# Control_Board_Control.net
KiCad netlist of a schematic drawn in Altium Designer
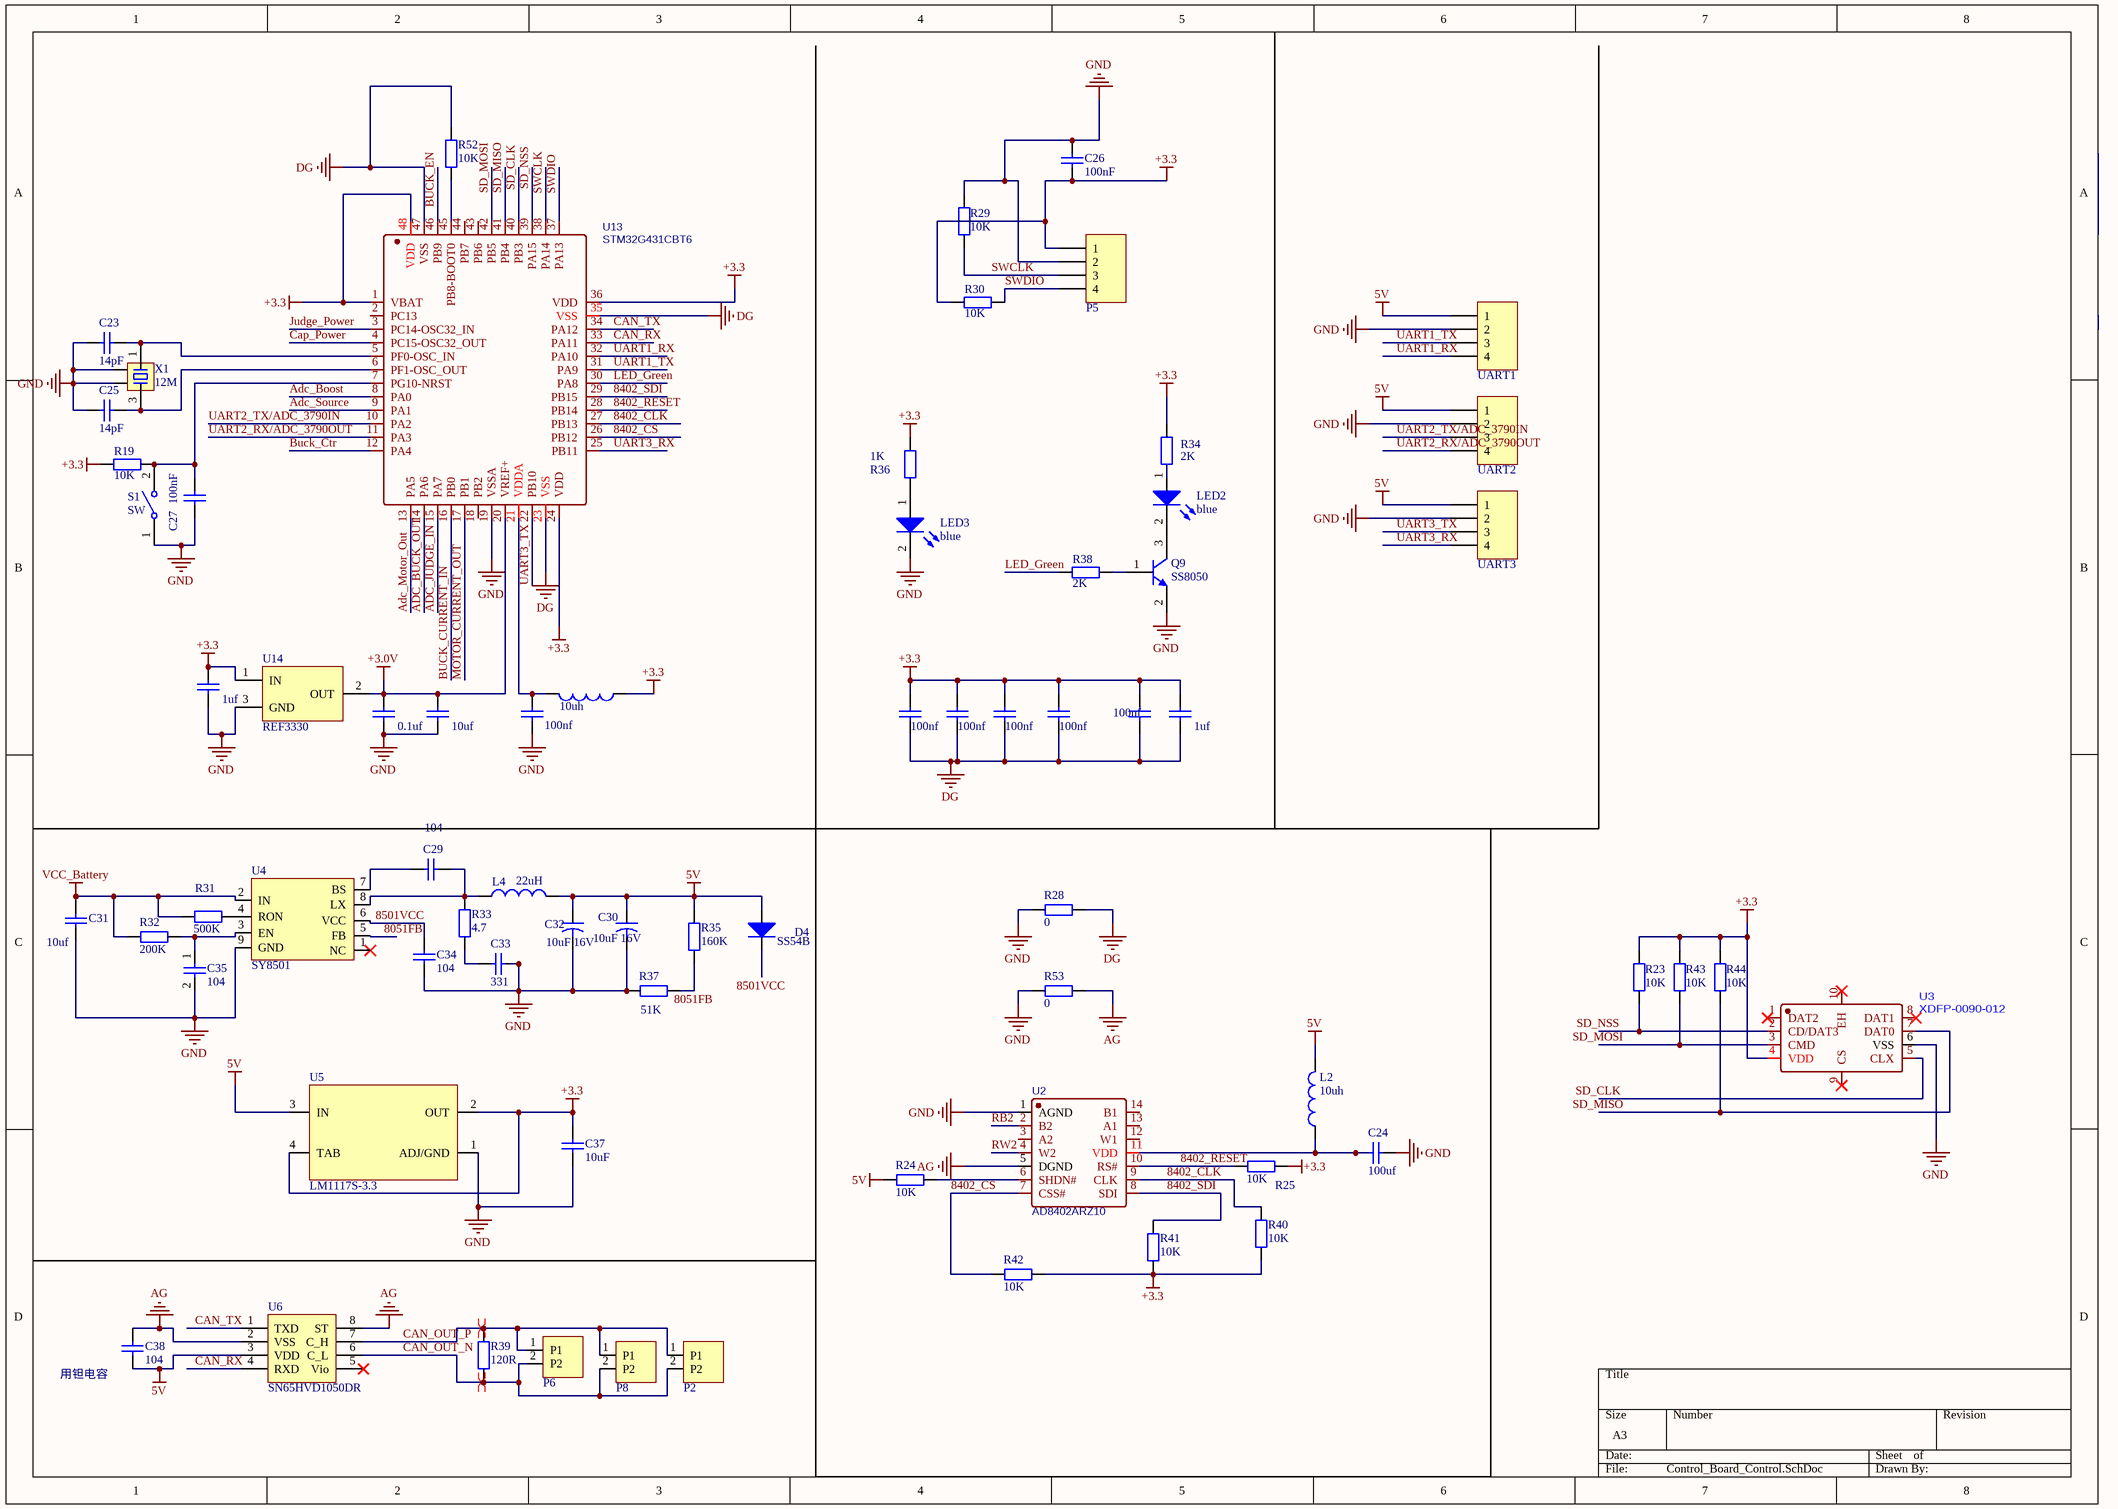
[diagram p0: Control_Board_Control.SchDoc]

(export (version "E")
  (design (tool "Eeschema 10.0.6"))
  (components
    (comp (ref "C23")
      (value "14pF")
      (footprint "c0402")
      (description "无极性电容")
      (fields (field (name "Comment") "27pf") (field (name "PUBLISHER") "Altium Limited"))
      (libsource (lib "Fszhang") (part "Cap"))
    )
    (comp (ref "C24")
      (value "100uf")
      (footprint "1210C")
      (description "无极性电容")
      (fields (field (name "PUBLISHER") "Altium Limited"))
      (libsource (lib "Fszhang") (part "Cap"))
    )
    (comp (ref "C25")
      (value "14pF")
      (footprint "c0402")
      (description "无极性电容")
      (fields (field (name "Comment") "27pf") (field (name "PUBLISHER") "Altium Limited"))
      (libsource (lib "Fszhang") (part "Cap"))
    )
    (comp (ref "C26")
      (value "100nF")
      (footprint "r0402")
      (description "无极性电容")
      (fields (field (name "PUBLISHER") "Altium Limited"))
      (libsource (lib "Fszhang") (part "Cap"))
    )
    (comp (ref "C27")
      (value "100nF")
      (footprint "c0402")
      (description "无极性电容")
      (fields (field (name "Comment") "100nf") (field (name "PUBLISHER") "Altium Limited"))
      (libsource (lib "Fszhang") (part "Cap"))
    )
    (comp (ref "C29")
      (value "104")
      (footprint "r0402")
      (description "无极性电容")
      (fields (field (name "PUBLISHER") "Altium Limited"))
      (libsource (lib "Fszhang") (part "Cap"))
    )
    (comp (ref "C30")
      (value "10uF 16V")
      (footprint "3216")
      (description "贴片电解")
      (fields (field (name "PUBLISHER") "Altium Limited"))
      (libsource (lib "Miscellaneous Devices") (part "Cap2"))
    )
    (comp (ref "C31")
      (value "10uf")
      (footprint "0805-1C")
      (description "无极性电容")
      (fields (field (name "PUBLISHER") "Altium Limited"))
      (libsource (lib "Fszhang") (part "Cap"))
    )
    (comp (ref "C32")
      (value "10uF 16V")
      (footprint "3216")
      (description "贴片电解")
      (fields (field (name "PUBLISHER") "Altium Limited"))
      (libsource (lib "Miscellaneous Devices") (part "Cap2"))
    )
    (comp (ref "C33")
      (value "331")
      (footprint "r0402")
      (description "无极性电容")
      (fields (field (name "PUBLISHER") "Altium Limited"))
      (libsource (lib "Fszhang") (part "Cap"))
    )
    (comp (ref "C34")
      (value "104")
      (footprint "r0402")
      (description "无极性电容")
      (fields (field (name "PUBLISHER") "Altium Limited"))
      (libsource (lib "Fszhang") (part "Cap"))
    )
    (comp (ref "C35")
      (value "104")
      (footprint "r0402")
      (description "贴片电容1206")
      (fields (field (name "C") "104"))
      (libsource (lib "原理图库") (part "CAP-W"))
    )
    (comp (ref "C36")
      (value "100nf")
      (footprint "c0402")
      (description "无极性电容")
      (fields (field (name "PUBLISHER") "Altium Limited"))
      (libsource (lib "Fszhang") (part "Cap"))
    )
    (comp (ref "C37")
      (value "10uF")
      (footprint "3216")
      (description "无极性电容")
      (fields (field (name "Comment") "10UF") (field (name "PUBLISHER") "Altium Limited"))
      (libsource (lib "Fszhang") (part "Cap"))
    )
    (comp (ref "C38")
      (value "104")
      (footprint "r0402")
      (description "贴片电容")
      (libsource (lib "0.1 - 电阻-电容-电感-电位器") (part "C"))
    )
    (comp (ref "C52")
      (value "100nf")
      (footprint "c0402")
      (description "无极性电容")
      (fields (field (name "PUBLISHER") "Altium Limited"))
      (libsource (lib "Fszhang") (part "Cap"))
    )
    (comp (ref "C53")
      (value "100nf")
      (footprint "c0402")
      (description "无极性电容")
      (fields (field (name "PUBLISHER") "Altium Limited"))
      (libsource (lib "Fszhang") (part "Cap"))
    )
    (comp (ref "C54")
      (value "100nf")
      (footprint "c0402")
      (description "无极性电容")
      (fields (field (name "PUBLISHER") "Altium Limited"))
      (libsource (lib "Fszhang") (part "Cap"))
    )
    (comp (ref "C55")
      (value "100nf")
      (footprint "c0402")
      (description "无极性电容")
      (fields (field (name "PUBLISHER") "Altium Limited"))
      (libsource (lib "Fszhang") (part "Cap"))
    )
    (comp (ref "C56")
      (value "100nf")
      (footprint "c0402")
      (description "无极性电容")
      (fields (field (name "PUBLISHER") "Altium Limited"))
      (libsource (lib "Fszhang") (part "Cap"))
    )
    (comp (ref "C57")
      (value "1uf")
      (footprint "c0402")
      (description "无极性电容")
      (fields (field (name "PUBLISHER") "Altium Limited"))
      (libsource (lib "Fszhang") (part "Cap"))
    )
    (comp (ref "C58")
      (value "1uf")
      (footprint "c0402")
      (description "无极性电容")
      (fields (field (name "PUBLISHER") "Altium Limited"))
      (libsource (lib "Fszhang") (part "Cap"))
    )
    (comp (ref "C63")
      (value "10uf")
      (footprint "c0402")
      (description "无极性电容")
      (fields (field (name "PUBLISHER") "Altium Limited"))
      (libsource (lib "Fszhang") (part "Cap"))
    )
    (comp (ref "C65")
      (value "0.1uf")
      (footprint "c0402")
      (description "无极性电容")
      (fields (field (name "PUBLISHER") "Altium Limited"))
      (libsource (lib "Fszhang") (part "Cap"))
    )
    (comp (ref "D4")
      (value "SS54B")
      (footprint "DO-214")
      (description "肖特基二极管")
      (fields (field (name "PUBLISHER") "Altium Limited"))
      (libsource (lib "Miscellaneous Devices") (part "Diode"))
    )
    (comp (ref "L2")
      (value "10uh")
      (footprint "l0805")
      (description "功率电感")
      (fields (field (name "PUBLISHER") "Altium Limited"))
      (libsource (lib "Miscellaneous Devices") (part "Inductor"))
    )
    (comp (ref "L4")
      (value "22uH")
      (footprint "CD54NP")
      (description "功率电感")
      (fields (field (name "PUBLISHER") "Altium Limited"))
      (libsource (lib "Miscellaneous Devices") (part "Inductor"))
    )
    (comp (ref "L8")
      (value "10uh")
      (footprint "l0805")
      (description "功率电感")
      (fields (field (name "PUBLISHER") "Altium Limited"))
      (libsource (lib "Miscellaneous Devices") (part "Inductor"))
    )
    (comp (ref "LED2")
      (value "LED_灯_黄")
      (footprint "led0805")
      (description "贴片LED")
      (fields (field (name "COLOR") "blue"))
      (libsource (lib "super_cap") (part "LED"))
    )
    (comp (ref "LED3")
      (value "LED_灯_黄")
      (footprint "led0805")
      (description "贴片LED")
      (fields (field (name "COLOR") "blue"))
      (libsource (lib "super_cap") (part "LED"))
    )
    (comp (ref "P2") (value "P2") (footprint "gh1.25") (libsource (lib "原理图库") (part "P2")))
    (comp (ref "P5")
      (value "Header 4")
      (footprint "gh1.25 4p 立贴")
      (description "排针")
      (fields (field (name "PUBLISHER") "Altium Limited"))
      (libsource (lib "super_cap") (part "Header 4"))
    )
    (comp (ref "P6") (value "P2") (footprint "gh1.25") (libsource (lib "原理图库") (part "P2")))
    (comp (ref "P8") (value "P2") (footprint "gh1.25") (libsource (lib "原理图库") (part "P2")))
    (comp (ref "Q9")
      (value "SS8050")
      (footprint "SOT-23")
      (description "NPN贴片三极管")
      (fields (field (name "PUBLISHER") "Altium Limited"))
      (libsource (lib "fszhang") (part "SS8050"))
    )
    (comp (ref "R19")
      (value "10K")
      (footprint "r0402")
      (description "贴片电阻")
      (fields (field (name "Comment") "10k") (field (name "PUBLISHER") "Altium Limited"))
      (libsource (lib "") (part "Res1_3"))
    )
    (comp (ref "R23")
      (value "10K")
      (footprint "R0402")
      (description "贴片电阻")
      (fields (field (name "PUBLISHER") "Altium Limited"))
      (libsource (lib "") (part "Res1_1"))
    )
    (comp (ref "R24")
      (value "10K")
      (footprint "r0402")
      (description "贴片电阻")
      (libsource (lib "super_cap") (part "R"))
    )
    (comp (ref "R25")
      (value "10K")
      (footprint "r0402")
      (description "贴片电阻")
      (libsource (lib "super_cap") (part "R"))
    )
    (comp (ref "R28")
      (value "0")
      (footprint "r0402")
      (description "贴片电阻")
      (libsource (lib "super_cap") (part "R"))
    )
    (comp (ref "R29")
      (value "10K")
      (footprint "r0402")
      (description "贴片电阻")
      (fields (field (name "PUBLISHER") "Altium Limited"))
      (libsource (lib "") (part "Res1_2"))
    )
    (comp (ref "R30")
      (value "10K")
      (footprint "r0402")
      (description "贴片电阻")
      (fields (field (name "PUBLISHER") "Altium Limited"))
      (libsource (lib "Fszhang") (part "Res1"))
    )
    (comp (ref "R31")
      (value "500K")
      (footprint "r0402")
      (description "贴片电阻")
      (libsource (lib "super_cap") (part "R"))
    )
    (comp (ref "R32")
      (value "200K")
      (footprint "r0402")
      (description "贴片电阻")
      (libsource (lib "super_cap") (part "R"))
    )
    (comp (ref "R33")
      (value "4.7")
      (footprint "r0402")
      (description "贴片电阻")
      (libsource (lib "super_cap") (part "R"))
    )
    (comp (ref "R34")
      (value "2K")
      (footprint "r0402")
      (description "贴片电阻")
      (fields (field (name "PUBLISHER") "Altium Limited"))
      (libsource (lib "") (part "Res1_2"))
    )
    (comp (ref "R35")
      (value "160K")
      (footprint "r0402")
      (description "贴片电阻")
      (libsource (lib "super_cap") (part "R"))
    )
    (comp (ref "R36")
      (value "1K")
      (footprint "r0402")
      (description "贴片电阻")
      (fields (field (name "PUBLISHER") "Altium Limited"))
      (libsource (lib "") (part "Res1_1"))
    )
    (comp (ref "R37")
      (value "51K")
      (footprint "r0402")
      (description "贴片电阻")
      (libsource (lib "super_cap") (part "R"))
    )
    (comp (ref "R38")
      (value "2K")
      (footprint "r0402")
      (description "贴片电阻")
      (fields (field (name "PUBLISHER") "Altium Limited"))
      (libsource (lib "Fszhang") (part "Res1"))
    )
    (comp (ref "R39")
      (value "120R")
      (footprint "r0402")
      (description "贴片电阻")
      (libsource (lib "0.1 - 电阻-电容-电感-电位器") (part "R"))
    )
    (comp (ref "R40")
      (value "10K")
      (footprint "r0402")
      (description "贴片电阻")
      (libsource (lib "super_cap") (part "R"))
    )
    (comp (ref "R41")
      (value "10K")
      (footprint "r0402")
      (description "贴片电阻")
      (libsource (lib "super_cap") (part "R"))
    )
    (comp (ref "R42")
      (value "10K")
      (footprint "r0402")
      (description "贴片电阻")
      (libsource (lib "super_cap") (part "R"))
    )
    (comp (ref "R43")
      (value "10K")
      (footprint "R0402")
      (description "贴片电阻")
      (fields (field (name "PUBLISHER") "Altium Limited"))
      (libsource (lib "") (part "Res1_1"))
    )
    (comp (ref "R44")
      (value "10K")
      (footprint "R0402")
      (description "贴片电阻")
      (fields (field (name "PUBLISHER") "Altium Limited"))
      (libsource (lib "") (part "Res1_1"))
    )
    (comp (ref "R52")
      (value "10K")
      (footprint "r0402")
      (description "贴片电阻")
      (libsource (lib "super_cap") (part "R"))
    )
    (comp (ref "R53")
      (value "0")
      (footprint "r0402")
      (description "贴片电阻")
      (libsource (lib "super_cap") (part "R"))
    )
    (comp (ref "S1") (value "SW") (footprint "KEY_SMD") (libsource (lib "super_cap") (part "SW")))
    (comp (ref "U2")
      (value "AD8402ARZ10")
      (footprint "SOIC14")
      (fields
        (field (name "BOM_SUPPLIER PART") "C652776")
        (field (name "BOM_MANUFACTURER PART") "AD8402ARZ100")
        (field (name "CONTRIBUTOR") "LCSC")
      )
      (libsource (lib "ofq") (part "AD8402ARZ100"))
    )
    (comp (ref "U3")
      (value "XDFP-0090-012")
      (footprint "SIM-SMD_LX_XDFP-0090-012")
      (libsource (lib "supercapbuck") (part "XDFP-0090-012"))
    )
    (comp (ref "U4")
      (value "SY8501")
      (footprint "SO8E")
      (description "电源管理芯片")
      (libsource (lib "super_cap") (part "SY8501"))
    )
    (comp (ref "U5")
      (value "LM1117S-3.3")
      (footprint "sot-223")
      (libsource (lib "super_cap") (part "LM1117S-3.3"))
    )
    (comp (ref "U6") (value "SN65HVD1050DR") (footprint "LM358") (libsource (lib "原理图库") (part "TLP250")))
    (comp (ref "U13")
      (value "STM32G431CBT6")
      (footprint "LQFP-48")
      (fields (field (name "BOM_SUPPLIER PART") "C529355") (field (name "CONTRIBUTOR") "LCSC"))
      (libsource (lib "ofq") (part "STM32G431CBT6"))
    )
    (comp (ref "U14") (value "REF3330") (footprint "sot23-3") (libsource (lib "ofq") (part "REF33")))
    (comp (ref "UART1")
      (value "Header 4")
      (footprint "gh1.25 4p 立贴")
      (description "排针")
      (fields (field (name "PUBLISHER") "Altium Limited"))
      (libsource (lib "super_cap") (part "Header 4"))
    )
    (comp (ref "UART2")
      (value "Header 4")
      (footprint "gh1.25 4p 立贴")
      (description "排针")
      (fields (field (name "PUBLISHER") "Altium Limited"))
      (libsource (lib "super_cap") (part "Header 4"))
    )
    (comp (ref "UART3")
      (value "Header 4")
      (footprint "gh1.25 4p 立贴")
      (description "排针")
      (fields (field (name "PUBLISHER") "Altium Limited"))
      (libsource (lib "super_cap") (part "Header 4"))
    )
    (comp (ref "X1")
      (value "12M")
      (footprint "XTAL-3225")
      (description "4脚无源晶振")
      (libsource (lib "super_cap") (part "XTAL-4P"))
    )
  )
  (nets
    (net (code "1") (name "+3.0V") (class "Default")
      (node (ref "C63") (pin "1") (pinfunction "1_1") (pintype "passive"))
      (node (ref "C65") (pin "1") (pinfunction "1_1") (pintype "passive"))
      (node (ref "U13") (pin "20") (pinfunction "VREF+_20") (pintype "passive"))
      (node (ref "U14") (pin "2") (pinfunction "OUT_2") (pintype "passive"))
    )
    (net (code "2") (name "+3.3") (class "Default")
      (node (ref "C26") (pin "2") (pinfunction "2_2") (pintype "passive"))
      (node (ref "C37") (pin "1") (pinfunction "1_1") (pintype "passive"))
      (node (ref "C52") (pin "1") (pinfunction "1_1") (pintype "passive"))
      (node (ref "C53") (pin "1") (pinfunction "1_1") (pintype "passive"))
      (node (ref "C54") (pin "1") (pinfunction "1_1") (pintype "passive"))
      (node (ref "C55") (pin "1") (pinfunction "1_1") (pintype "passive"))
      (node (ref "C56") (pin "1") (pinfunction "1_1") (pintype "passive"))
      (node (ref "C57") (pin "1") (pinfunction "1_1") (pintype "passive"))
      (node (ref "C58") (pin "1") (pinfunction "1_1") (pintype "passive"))
      (node (ref "L8") (pin "1") (pinfunction "1_1") (pintype "passive"))
      (node (ref "P5") (pin "1") (pinfunction "1_1") (pintype "passive"))
      (node (ref "R19") (pin "2") (pinfunction "2_2") (pintype "passive"))
      (node (ref "R23") (pin "2") (pinfunction "2_2") (pintype "passive"))
      (node (ref "R25") (pin "1") (pinfunction "1_1") (pintype "passive"))
      (node (ref "R30") (pin "1") (pinfunction "1_1") (pintype "passive"))
      (node (ref "R34") (pin "1") (pinfunction "1_1") (pintype "passive"))
      (node (ref "R36") (pin "2") (pinfunction "2_2") (pintype "passive"))
      (node (ref "R40") (pin "2") (pinfunction "2_2") (pintype "passive"))
      (node (ref "R41") (pin "2") (pinfunction "2_2") (pintype "passive"))
      (node (ref "R42") (pin "2") (pinfunction "2_2") (pintype "passive"))
      (node (ref "R43") (pin "2") (pinfunction "2_2") (pintype "passive"))
      (node (ref "R44") (pin "2") (pinfunction "2_2") (pintype "passive"))
      (node (ref "U13") (pin "1") (pinfunction "VBAT_1") (pintype "passive"))
      (node (ref "U13") (pin "24") (pinfunction "VDD_24") (pintype "passive"))
      (node (ref "U13") (pin "36") (pinfunction "VDD_36") (pintype "passive"))
      (node (ref "U13") (pin "48") (pinfunction "VDD_48") (pintype "passive"))
      (node (ref "U14") (pin "1") (pinfunction "IN_1") (pintype "passive"))
      (node (ref "U3") (pin "4") (pinfunction "VDD_4") (pintype "passive"))
      (node (ref "U5") (pin "2") (pinfunction "OUT_2") (pintype "passive"))
      (node (ref "U5") (pin "4") (pinfunction "TAB_4") (pintype "passive"))
    )
    (net (code "3") (name "/8051FB") (class "Default")
      (node (ref "R35") (pin "2") (pinfunction "2_2") (pintype "passive"))
      (node (ref "R37") (pin "2") (pinfunction "2_2") (pintype "passive"))
      (node (ref "U4") (pin "5") (pinfunction "FB_5") (pintype "passive"))
    )
    (net (code "4") (name "/8402_CLK") (class "Default")
      (node (ref "R40") (pin "1") (pinfunction "1_1") (pintype "passive"))
      (node (ref "U13") (pin "27") (pinfunction "PB13_27") (pintype "passive"))
      (node (ref "U2") (pin "9") (pinfunction "CLK_9") (pintype "passive"))
    )
    (net (code "5") (name "/8402_CS") (class "Default")
      (node (ref "R42") (pin "1") (pinfunction "1_1") (pintype "passive"))
      (node (ref "U13") (pin "26") (pinfunction "PB12_26") (pintype "passive"))
      (node (ref "U2") (pin "7") (pinfunction "CSS#_7") (pintype "passive"))
    )
    (net (code "6") (name "/8402_RESET") (class "Default")
      (node (ref "R25") (pin "2") (pinfunction "2_2") (pintype "passive"))
      (node (ref "U13") (pin "28") (pinfunction "PB14_28") (pintype "passive"))
      (node (ref "U2") (pin "10") (pinfunction "RS#_10") (pintype "passive"))
    )
    (net (code "7") (name "/8402_SDI") (class "Default")
      (node (ref "R41") (pin "1") (pinfunction "1_1") (pintype "passive"))
      (node (ref "U13") (pin "29") (pinfunction "PB15_29") (pintype "passive"))
      (node (ref "U2") (pin "8") (pinfunction "SDI_8") (pintype "passive"))
    )
    (net (code "8") (name "/8501VCC") (class "Default")
      (node (ref "C34") (pin "1") (pinfunction "1_1") (pintype "passive"))
      (node (ref "D4") (pin "2") (pinfunction "K_2") (pintype "passive"))
      (node (ref "U4") (pin "6") (pinfunction "VCC_6") (pintype "passive"))
    )
    (net (code "9") (name "/ADC_BUCK_OUT") (class "Default")
      (node (ref "U13") (pin "14") (pinfunction "PA6_14") (pintype "passive"))
    )
    (net (code "10") (name "/ADC_JUDGE_IN") (class "Default")
      (node (ref "U13") (pin "15") (pinfunction "PA7_15") (pintype "passive"))
    )
    (net (code "11") (name "/Adc_Boost") (class "Default")
      (node (ref "U13") (pin "8") (pinfunction "PA0_8") (pintype "passive"))
    )
    (net (code "12") (name "/Adc_Motor_Out") (class "Default")
      (node (ref "U13") (pin "13") (pinfunction "PA5_13") (pintype "passive"))
    )
    (net (code "13") (name "/Adc_Source") (class "Default")
      (node (ref "U13") (pin "9") (pinfunction "PA1_9") (pintype "passive"))
    )
    (net (code "14") (name "/BUCK_CURRENT_IN") (class "Default")
      (node (ref "U13") (pin "16") (pinfunction "PB0_16") (pintype "passive"))
    )
    (net (code "15") (name "/BUCK_EN") (class "Default")
      (node (ref "U13") (pin "46") (pinfunction "PB9_46") (pintype "passive"))
    )
    (net (code "16") (name "/Buck_Ctr") (class "Default")
      (node (ref "U13") (pin "12") (pinfunction "PA4_12") (pintype "passive"))
    )
    (net (code "17") (name "/CAN_OUT_N") (class "Default")
      (node (ref "P2") (pin "2") (pinfunction "P2_2") (pintype "passive"))
      (node (ref "P6") (pin "2") (pinfunction "P2_2") (pintype "passive"))
      (node (ref "P8") (pin "2") (pinfunction "P2_2") (pintype "passive"))
      (node (ref "R39") (pin "1") (pinfunction "1_1") (pintype "passive"))
      (node (ref "U6") (pin "6") (pinfunction "C_L_6") (pintype "passive"))
    )
    (net (code "18") (name "/CAN_OUT_P") (class "Default")
      (node (ref "P2") (pin "1") (pinfunction "P1_1") (pintype "passive"))
      (node (ref "P6") (pin "1") (pinfunction "P1_1") (pintype "passive"))
      (node (ref "P8") (pin "1") (pinfunction "P1_1") (pintype "passive"))
      (node (ref "R39") (pin "2") (pinfunction "2_2") (pintype "passive"))
      (node (ref "U6") (pin "7") (pinfunction "C_H_7") (pintype "passive"))
    )
    (net (code "19") (name "/CAN_RX") (class "Default")
      (node (ref "U13") (pin "33") (pinfunction "PA11_33") (pintype "passive"))
      (node (ref "U6") (pin "4") (pinfunction "RXD_4") (pintype "passive"))
    )
    (net (code "20") (name "/CAN_TX") (class "Default")
      (node (ref "U13") (pin "34") (pinfunction "PA12_34") (pintype "passive"))
      (node (ref "U6") (pin "1") (pinfunction "TXD_1") (pintype "passive"))
    )
    (net (code "21") (name "/Cap_Power") (class "Default")
      (node (ref "U13") (pin "4") (pinfunction "PC15-OSC32_OUT_4") (pintype "passive"))
    )
    (net (code "22") (name "/Judge_Power") (class "Default")
      (node (ref "U13") (pin "3") (pinfunction "PC14-OSC32_IN_3") (pintype "passive"))
    )
    (net (code "23") (name "/LED_Green") (class "Default")
      (node (ref "R38") (pin "1") (pinfunction "1_1") (pintype "passive"))
      (node (ref "U13") (pin "30") (pinfunction "PA8_30") (pintype "passive"))
    )
    (net (code "24") (name "/MOTOR_CURRENT_OUT") (class "Default")
      (node (ref "U13") (pin "17") (pinfunction "PB1_17") (pintype "passive"))
    )
    (net (code "25") (name "/RB2") (class "Default")
      (node (ref "U2") (pin "2") (pinfunction "B2_2") (pintype "passive"))
    )
    (net (code "26") (name "/RW2") (class "Default")
      (node (ref "U2") (pin "4") (pinfunction "W2_4") (pintype "passive"))
    )
    (net (code "27") (name "/SD_CLK") (class "Default")
      (node (ref "U13") (pin "40") (pinfunction "PB3_40") (pintype "passive"))
      (node (ref "U3") (pin "5") (pinfunction "CLX_5") (pintype "passive"))
    )
    (net (code "28") (name "/SD_MISO") (class "Default")
      (node (ref "R44") (pin "1") (pinfunction "1_1") (pintype "passive"))
      (node (ref "U13") (pin "41") (pinfunction "PB4_41") (pintype "passive"))
      (node (ref "U3") (pin "7") (pinfunction "DAT0_7") (pintype "passive"))
    )
    (net (code "29") (name "/SD_MOSI") (class "Default")
      (node (ref "R43") (pin "1") (pinfunction "1_1") (pintype "passive"))
      (node (ref "U13") (pin "42") (pinfunction "PB5_42") (pintype "passive"))
      (node (ref "U3") (pin "3") (pinfunction "CMD_3") (pintype "passive"))
    )
    (net (code "30") (name "/SD_NSS") (class "Default")
      (node (ref "R23") (pin "1") (pinfunction "1_1") (pintype "passive"))
      (node (ref "U13") (pin "39") (pinfunction "PA15_39") (pintype "passive"))
      (node (ref "U3") (pin "2") (pinfunction "CD/DAT3_2") (pintype "passive"))
    )
    (net (code "31") (name "/SWCLK") (class "Default")
      (node (ref "P5") (pin "3") (pinfunction "3_3") (pintype "passive"))
      (node (ref "R29") (pin "2") (pinfunction "2_2") (pintype "passive"))
      (node (ref "U13") (pin "38") (pinfunction "PA14_38") (pintype "passive"))
    )
    (net (code "32") (name "/SWDIO") (class "Default")
      (node (ref "P5") (pin "4") (pinfunction "4_4") (pintype "passive"))
      (node (ref "R30") (pin "2") (pinfunction "2_2") (pintype "passive"))
      (node (ref "U13") (pin "37") (pinfunction "PA13_37") (pintype "passive"))
    )
    (net (code "33") (name "/UART1_RX") (class "Default")
      (node (ref "U13") (pin "32") (pinfunction "PA10_32") (pintype "passive"))
      (node (ref "UART1") (pin "4") (pinfunction "4_4") (pintype "passive"))
    )
    (net (code "34") (name "/UART1_TX") (class "Default")
      (node (ref "U13") (pin "31") (pinfunction "PA9_31") (pintype "passive"))
      (node (ref "UART1") (pin "3") (pinfunction "3_3") (pintype "passive"))
    )
    (net (code "35") (name "/UART2_RX{slash}ADC_3790OUT") (class "Default")
      (node (ref "U13") (pin "11") (pinfunction "PA3_11") (pintype "passive"))
      (node (ref "UART2") (pin "4") (pinfunction "4_4") (pintype "passive"))
    )
    (net (code "36") (name "/UART2_TX{slash}ADC_3790IN") (class "Default")
      (node (ref "U13") (pin "10") (pinfunction "PA2_10") (pintype "passive"))
      (node (ref "UART2") (pin "3") (pinfunction "3_3") (pintype "passive"))
    )
    (net (code "37") (name "/UART3_RX") (class "Default")
      (node (ref "U13") (pin "25") (pinfunction "PB11_25") (pintype "passive"))
      (node (ref "UART3") (pin "4") (pinfunction "4_4") (pintype "passive"))
    )
    (net (code "38") (name "/UART3_TX") (class "Default")
      (node (ref "U13") (pin "22") (pinfunction "PB10_22") (pintype "passive"))
      (node (ref "UART3") (pin "3") (pinfunction "3_3") (pintype "passive"))
    )
    (net (code "39") (name "5V") (class "Default")
      (node (ref "C30") (pin "1") (pinfunction "1_1") (pintype "passive"))
      (node (ref "C32") (pin "1") (pinfunction "1_1") (pintype "passive"))
      (node (ref "C38") (pin "2") (pinfunction "2_2") (pintype "passive"))
      (node (ref "D4") (pin "1") (pinfunction "A_1") (pintype "passive"))
      (node (ref "L2") (pin "2") (pinfunction "2_2") (pintype "passive"))
      (node (ref "L4") (pin "2") (pinfunction "2_2") (pintype "passive"))
      (node (ref "R24") (pin "2") (pinfunction "2_2") (pintype "passive"))
      (node (ref "R35") (pin "1") (pinfunction "1_1") (pintype "passive"))
      (node (ref "U5") (pin "3") (pinfunction "IN_3") (pintype "passive"))
      (node (ref "U6") (pin "3") (pinfunction "VDD_3") (pintype "passive"))
      (node (ref "UART1") (pin "1") (pinfunction "1_1") (pintype "passive"))
      (node (ref "UART2") (pin "1") (pinfunction "1_1") (pintype "passive"))
      (node (ref "UART3") (pin "1") (pinfunction "1_1") (pintype "passive"))
    )
    (net (code "40") (name "AG") (class "Default")
      (node (ref "C38") (pin "1") (pinfunction "1_1") (pintype "passive"))
      (node (ref "R53") (pin "2") (pinfunction "2_2") (pintype "passive"))
      (node (ref "U2") (pin "5") (pinfunction "DGND_5") (pintype "passive"))
      (node (ref "U6") (pin "2") (pinfunction "VSS_2") (pintype "passive"))
      (node (ref "U6") (pin "8") (pinfunction "ST_8") (pintype "passive"))
    )
    (net (code "41") (name "DG") (class "Default")
      (node (ref "C52") (pin "2") (pinfunction "2_2") (pintype "passive"))
      (node (ref "C53") (pin "2") (pinfunction "2_2") (pintype "passive"))
      (node (ref "C54") (pin "2") (pinfunction "2_2") (pintype "passive"))
      (node (ref "C55") (pin "2") (pinfunction "2_2") (pintype "passive"))
      (node (ref "C56") (pin "2") (pinfunction "2_2") (pintype "passive"))
      (node (ref "C57") (pin "2") (pinfunction "2_2") (pintype "passive"))
      (node (ref "R28") (pin "2") (pinfunction "2_2") (pintype "passive"))
      (node (ref "R52") (pin "2") (pinfunction "2_2") (pintype "passive"))
      (node (ref "U13") (pin "23") (pinfunction "VSS_23") (pintype "passive"))
      (node (ref "U13") (pin "35") (pinfunction "VSS_35") (pintype "passive"))
      (node (ref "U13") (pin "47") (pinfunction "VSS_47") (pintype "passive"))
    )
    (net (code "42") (name "GND") (class "Default")
      (node (ref "C23") (pin "2") (pinfunction "2_2") (pintype "passive"))
      (node (ref "C24") (pin "1") (pinfunction "1_1") (pintype "passive"))
      (node (ref "C25") (pin "2") (pinfunction "2_2") (pintype "passive"))
      (node (ref "C26") (pin "1") (pinfunction "1_1") (pintype "passive"))
      (node (ref "C27") (pin "1") (pinfunction "1_1") (pintype "passive"))
      (node (ref "C30") (pin "2") (pinfunction "2_2") (pintype "passive"))
      (node (ref "C31") (pin "2") (pinfunction "2_2") (pintype "passive"))
      (node (ref "C32") (pin "2") (pinfunction "2_2") (pintype "passive"))
      (node (ref "C33") (pin "1") (pinfunction "1_1") (pintype "passive"))
      (node (ref "C34") (pin "2") (pinfunction "2_2") (pintype "passive"))
      (node (ref "C35") (pin "2") (pinfunction "2_2") (pintype "passive"))
      (node (ref "C36") (pin "2") (pinfunction "2_2") (pintype "passive"))
      (node (ref "C37") (pin "2") (pinfunction "2_2") (pintype "passive"))
      (node (ref "C58") (pin "2") (pinfunction "2_2") (pintype "passive"))
      (node (ref "C63") (pin "2") (pinfunction "2_2") (pintype "passive"))
      (node (ref "C65") (pin "2") (pinfunction "2_2") (pintype "passive"))
      (node (ref "LED3") (pin "2") (pinfunction "K_2") (pintype "passive"))
      (node (ref "P5") (pin "2") (pinfunction "2_2") (pintype "passive"))
      (node (ref "Q9") (pin "2") (pinfunction "E_2") (pintype "passive"))
      (node (ref "R28") (pin "1") (pinfunction "1_1") (pintype "passive"))
      (node (ref "R29") (pin "1") (pinfunction "1_1") (pintype "passive"))
      (node (ref "R37") (pin "1") (pinfunction "1_1") (pintype "passive"))
      (node (ref "R53") (pin "1") (pinfunction "1_1") (pintype "passive"))
      (node (ref "S1") (pin "1") (pinfunction "COMMON_1") (pintype "passive"))
      (node (ref "U13") (pin "19") (pinfunction "VSSA_19") (pintype "passive"))
      (node (ref "U14") (pin "3") (pinfunction "GND_3") (pintype "passive"))
      (node (ref "U2") (pin "1") (pinfunction "AGND_1") (pintype "passive"))
      (node (ref "U3") (pin "6") (pinfunction "VSS_6") (pintype "passive"))
      (node (ref "U4") (pin "9") (pinfunction "GND_9") (pintype "passive"))
      (node (ref "U5") (pin "1") (pinfunction "ADJ/GND_1") (pintype "passive"))
      (node (ref "UART1") (pin "2") (pinfunction "2_2") (pintype "passive"))
      (node (ref "UART2") (pin "2") (pinfunction "2_2") (pintype "passive"))
      (node (ref "UART3") (pin "2") (pinfunction "2_2") (pintype "passive"))
      (node (ref "X1") (pin "2") (pinfunction "2_2") (pintype "passive"))
      (node (ref "X1") (pin "4") (pinfunction "4_4") (pintype "passive"))
    )
    (net (code "43") (name "Net-(C33-Pad2)") (class "Default")
      (node (ref "C33") (pin "2") (pinfunction "2_2") (pintype "passive"))
      (node (ref "R33") (pin "2") (pinfunction "2_2") (pintype "passive"))
    )
    (net (code "44") (name "Net-(LED2-A)") (class "Default")
      (node (ref "LED2") (pin "1") (pinfunction "A_1") (pintype "passive"))
      (node (ref "R34") (pin "2") (pinfunction "2_2") (pintype "passive"))
    )
    (net (code "45") (name "Net-(LED2-K)") (class "Default")
      (node (ref "LED2") (pin "2") (pinfunction "K_2") (pintype "passive"))
      (node (ref "Q9") (pin "3") (pinfunction "C_3") (pintype "passive"))
    )
    (net (code "46") (name "Net-(LED3-A)") (class "Default")
      (node (ref "LED3") (pin "1") (pinfunction "A_1") (pintype "passive"))
      (node (ref "R36") (pin "1") (pinfunction "1_1") (pintype "passive"))
    )
    (net (code "47") (name "Net-(Q9-B)") (class "Default")
      (node (ref "Q9") (pin "1") (pinfunction "B_1") (pintype "passive"))
      (node (ref "R38") (pin "2") (pinfunction "2_2") (pintype "passive"))
    )
    (net (code "48") (name "Net-(S1-NO)") (class "Default")
      (node (ref "C27") (pin "2") (pinfunction "2_2") (pintype "passive"))
      (node (ref "R19") (pin "1") (pinfunction "1_1") (pintype "passive"))
      (node (ref "S1") (pin "2") (pinfunction "NO_2") (pintype "passive"))
      (node (ref "U13") (pin "7") (pinfunction "PG10-NRST_7") (pintype "passive"))
    )
    (net (code "49") (name "Net-(U2-SHDN#)") (class "Default")
      (node (ref "R24") (pin "1") (pinfunction "1_1") (pintype "passive"))
      (node (ref "U2") (pin "6") (pinfunction "SHDN#_6") (pintype "passive"))
    )
    (net (code "50") (name "Net-(U2-VDD)") (class "Default")
      (node (ref "C24") (pin "2") (pinfunction "2_2") (pintype "passive"))
      (node (ref "L2") (pin "1") (pinfunction "1_1") (pintype "passive"))
      (node (ref "U2") (pin "11") (pinfunction "VDD_11") (pintype "passive"))
    )
    (net (code "51") (name "Net-(U4-BS)") (class "Default")
      (node (ref "C29") (pin "2") (pinfunction "2_2") (pintype "passive"))
      (node (ref "U4") (pin "7") (pinfunction "BS_7") (pintype "passive"))
    )
    (net (code "52") (name "Net-(U4-EN)") (class "Default")
      (node (ref "C35") (pin "1") (pinfunction "1_1") (pintype "passive"))
      (node (ref "R32") (pin "1") (pinfunction "1_1") (pintype "passive"))
      (node (ref "U4") (pin "3") (pinfunction "EN_3") (pintype "passive"))
    )
    (net (code "53") (name "Net-(U4-LX)") (class "Default")
      (node (ref "C29") (pin "1") (pinfunction "1_1") (pintype "passive"))
      (node (ref "L4") (pin "1") (pinfunction "1_1") (pintype "passive"))
      (node (ref "R33") (pin "1") (pinfunction "1_1") (pintype "passive"))
      (node (ref "U4") (pin "8") (pinfunction "LX_8") (pintype "passive"))
    )
    (net (code "54") (name "Net-(U4-RON)") (class "Default")
      (node (ref "R31") (pin "1") (pinfunction "1_1") (pintype "passive"))
      (node (ref "U4") (pin "4") (pinfunction "RON_4") (pintype "passive"))
    )
    (net (code "55") (name "Net-(U13-PB8-BOOT0)") (class "Default")
      (node (ref "R52") (pin "1") (pinfunction "1_1") (pintype "passive"))
      (node (ref "U13") (pin "45") (pinfunction "PB8-BOOT0_45") (pintype "passive"))
    )
    (net (code "56") (name "Net-(U13-PF0-OSC_IN)") (class "Default")
      (node (ref "C23") (pin "1") (pinfunction "1_1") (pintype "passive"))
      (node (ref "U13") (pin "5") (pinfunction "PF0-OSC_IN_5") (pintype "passive"))
      (node (ref "X1") (pin "1") (pinfunction "1_1") (pintype "passive"))
    )
    (net (code "57") (name "Net-(U13-PF1-OSC_OUT)") (class "Default")
      (node (ref "C25") (pin "1") (pinfunction "1_1") (pintype "passive"))
      (node (ref "U13") (pin "6") (pinfunction "PF1-OSC_OUT_6") (pintype "passive"))
      (node (ref "X1") (pin "3") (pinfunction "3_3") (pintype "passive"))
    )
    (net (code "58") (name "Net-(U13-VDDA)") (class "Default")
      (node (ref "C36") (pin "1") (pinfunction "1_1") (pintype "passive"))
      (node (ref "L8") (pin "2") (pinfunction "2_2") (pintype "passive"))
      (node (ref "U13") (pin "21") (pinfunction "VDDA_21") (pintype "passive"))
    )
    (net (code "59") (name "VCC_Battery") (class "Default")
      (node (ref "C31") (pin "1") (pinfunction "1_1") (pintype "passive"))
      (node (ref "R31") (pin "2") (pinfunction "2_2") (pintype "passive"))
      (node (ref "R32") (pin "2") (pinfunction "2_2") (pintype "passive"))
      (node (ref "U4") (pin "2") (pinfunction "IN_2") (pintype "passive"))
    )
    (net (code "60") (name "unconnected-(U2-A1-Pad13)") (class "Default")
      (node (ref "U2") (pin "13") (pinfunction "A1_13") (pintype "passive"))
    )
    (net (code "61") (name "unconnected-(U2-A2-Pad3)") (class "Default")
      (node (ref "U2") (pin "3") (pinfunction "A2_3") (pintype "passive"))
    )
    (net (code "62") (name "unconnected-(U2-B1-Pad14)") (class "Default")
      (node (ref "U2") (pin "14") (pinfunction "B1_14") (pintype "passive"))
    )
    (net (code "63") (name "unconnected-(U2-W1-Pad12)") (class "Default")
      (node (ref "U2") (pin "12") (pinfunction "W1_12") (pintype "passive"))
    )
    (net (code "64") (name "unconnected-(U3-CS-Pad9)") (class "Default")
      (node (ref "U3") (pin "9") (pinfunction "CS_9") (pintype "passive+no_connect"))
    )
    (net (code "65") (name "unconnected-(U3-DAT1-Pad8)") (class "Default")
      (node (ref "U3") (pin "8") (pinfunction "DAT1_8") (pintype "passive+no_connect"))
    )
    (net (code "66") (name "unconnected-(U3-DAT2-Pad1)") (class "Default")
      (node (ref "U3") (pin "1") (pinfunction "DAT2_1") (pintype "passive+no_connect"))
    )
    (net (code "67") (name "unconnected-(U3-EH-Pad10)") (class "Default")
      (node (ref "U3") (pin "10") (pinfunction "EH_10") (pintype "passive+no_connect"))
    )
    (net (code "68") (name "unconnected-(U4-NC-Pad1)") (class "Default")
      (node (ref "U4") (pin "1") (pinfunction "NC_1") (pintype "passive+no_connect"))
    )
    (net (code "69") (name "unconnected-(U6-Vio-Pad5)") (class "Default")
      (node (ref "U6") (pin "5") (pinfunction "Vio_5") (pintype "passive+no_connect"))
    )
    (net (code "70") (name "unconnected-(U13-PB2-Pad18)") (class "Default")
      (node (ref "U13") (pin "18") (pinfunction "PB2_18") (pintype "passive"))
    )
    (net (code "71") (name "unconnected-(U13-PB6-Pad43)") (class "Default")
      (node (ref "U13") (pin "43") (pinfunction "PB6_43") (pintype "passive"))
    )
    (net (code "72") (name "unconnected-(U13-PB7-Pad44)") (class "Default")
      (node (ref "U13") (pin "44") (pinfunction "PB7_44") (pintype "passive"))
    )
    (net (code "73") (name "unconnected-(U13-PC13-Pad2)") (class "Default")
      (node (ref "U13") (pin "2") (pinfunction "PC13_2") (pintype "passive"))
    )
  )
)
